# 2_interface.net
KiCad netlist of a schematic drawn in Altium Designer
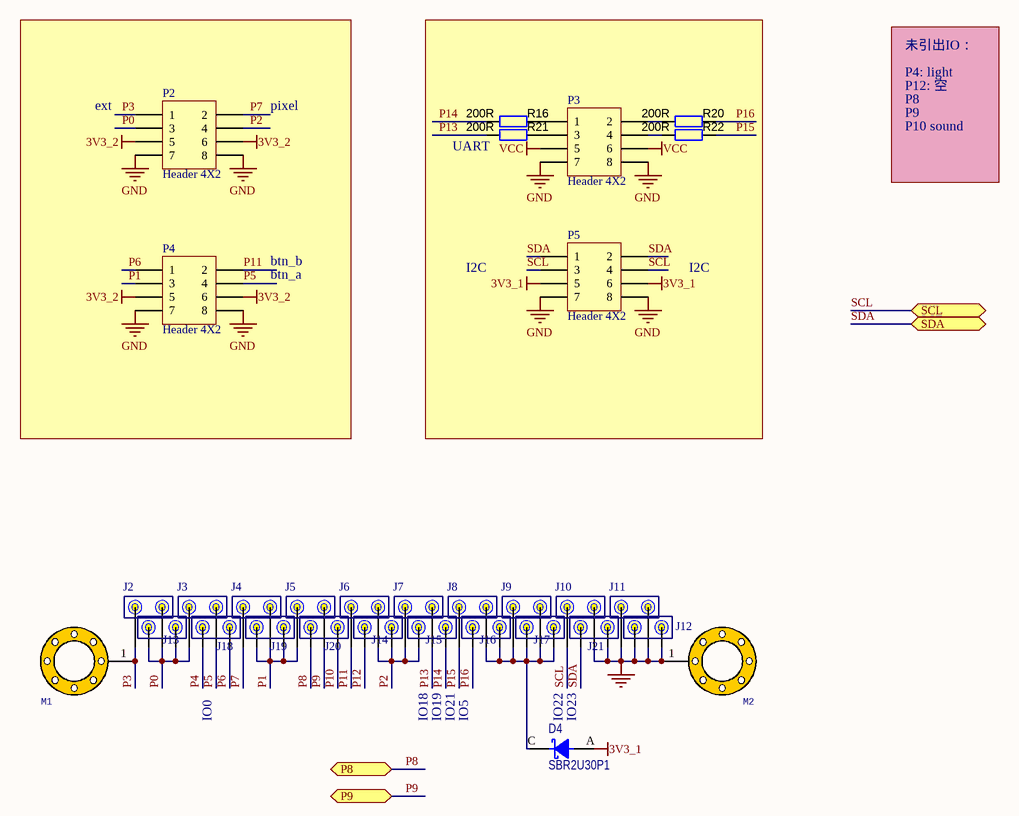
[diagram p0: 2.interface.SchDoc]

(export (version "E")
  (design (tool "Eeschema 10.0.6"))
  (components
    (comp (ref "D4")
      (value "SBR2U30P1")
      (footprint "POWERDI123")
      (fields (field (name "PARTNUMBER") "?") (field (name "PUBLISHER") "Altium Limited"))
      (libsource (lib "03.常用器件") (part "Diode_Schottky"))
    )
    (comp (ref "J2") (value "~") (footprint "顶针座子（2.54MM）") (libsource (lib "Schlib1") (part "pogopin")))
    (comp (ref "J3") (value "~") (footprint "顶针座子（2.54MM）") (libsource (lib "Schlib1") (part "pogopin")))
    (comp (ref "J4") (value "~") (footprint "顶针座子（2.54MM）") (libsource (lib "Schlib1") (part "pogopin")))
    (comp (ref "J5") (value "~") (footprint "顶针座子（2.54MM）") (libsource (lib "Schlib1") (part "pogopin")))
    (comp (ref "J6") (value "~") (footprint "顶针座子（2.54MM）") (libsource (lib "Schlib1") (part "pogopin")))
    (comp (ref "J7") (value "~") (footprint "顶针座子（2.54MM）") (libsource (lib "Schlib1") (part "pogopin")))
    (comp (ref "J8") (value "~") (footprint "顶针座子（2.54MM）") (libsource (lib "Schlib1") (part "pogopin")))
    (comp (ref "J9") (value "~") (footprint "顶针座子（2.54MM）") (libsource (lib "Schlib1") (part "pogopin")))
    (comp (ref "J10") (value "~") (footprint "顶针座子（2.54MM）") (libsource (lib "Schlib1") (part "pogopin")))
    (comp (ref "J11") (value "~") (footprint "顶针座子（2.54MM）") (libsource (lib "Schlib1") (part "pogopin")))
    (comp (ref "J12") (value "~") (footprint "顶针座子（2.54MM）") (libsource (lib "Schlib1") (part "pogopin_32")))
    (comp (ref "J13") (value "~") (footprint "顶针座子（2.54MM）") (libsource (lib "Schlib1") (part "pogopin_32")))
    (comp (ref "J14") (value "~") (footprint "顶针座子（2.54MM）") (libsource (lib "Schlib1") (part "pogopin_32")))
    (comp (ref "J15") (value "~") (footprint "顶针座子（2.54MM）") (libsource (lib "Schlib1") (part "pogopin_32")))
    (comp (ref "J16") (value "~") (footprint "顶针座子（2.54MM）") (libsource (lib "Schlib1") (part "pogopin_32")))
    (comp (ref "J17") (value "~") (footprint "顶针座子（2.54MM）") (libsource (lib "Schlib1") (part "pogopin_32")))
    (comp (ref "J18") (value "~") (footprint "顶针座子（2.54MM）") (libsource (lib "Schlib1") (part "pogopin_32")))
    (comp (ref "J19") (value "~") (footprint "顶针座子（2.54MM）") (libsource (lib "Schlib1") (part "pogopin_32")))
    (comp (ref "J20") (value "~") (footprint "顶针座子（2.54MM）") (libsource (lib "Schlib1") (part "pogopin_32")))
    (comp (ref "J21") (value "~") (footprint "顶针座子（2.54MM）") (libsource (lib "Schlib1") (part "pogopin_32")))
    (comp (ref "M1") (value "~") (footprint "3MM螺丝孔") (libsource (lib "labplus-connector") (part "screw")))
    (comp (ref "M2") (value "~") (footprint "3MM螺丝孔") (libsource (lib "labplus-connector") (part "screw")))
    (comp (ref "P2")
      (value "Header 4X2")
      (footprint "HDR2X4")
      (description "Header, 4-Pin, Dual row")
      (fields (field (name "PUBLISHER") "Altium Limited"))
      (libsource (lib "Miscellaneous Connectors") (part "Header 4X2"))
    )
    (comp (ref "P3")
      (value "Header 4X2")
      (footprint "HDR2X4")
      (description "Header, 4-Pin, Dual row")
      (fields (field (name "PUBLISHER") "Altium Limited"))
      (libsource (lib "Miscellaneous Connectors") (part "Header 4X2"))
    )
    (comp (ref "P4")
      (value "Header 4X2")
      (footprint "HDR2X4")
      (description "Header, 4-Pin, Dual row")
      (fields (field (name "PUBLISHER") "Altium Limited"))
      (libsource (lib "Miscellaneous Connectors") (part "Header 4X2"))
    )
    (comp (ref "P5")
      (value "Header 4X2")
      (footprint "HDR2X4")
      (description "Header, 4-Pin, Dual row")
      (fields (field (name "PUBLISHER") "Altium Limited"))
      (libsource (lib "Miscellaneous Connectors") (part "Header 4X2"))
    )
    (comp (ref "R16")
      (value "200R")
      (footprint "0402")
      (description "RES, 1.0k ohm, 5%, 0.1W, 0603")
      (fields
        (field (name "PARTNUMBER") "RC0603JR-071KL")
        (field (name "MANUFACTURER") "Yageo America")
        (field (name "PUBLISHER") "Texas Instruments")
      )
      (libsource (lib "03.常用器件") (part "RES1"))
    )
    (comp (ref "R20")
      (value "200R")
      (footprint "0402")
      (description "RES, 1.0k ohm, 5%, 0.1W, 0603")
      (fields
        (field (name "PARTNUMBER") "RC0603JR-071KL")
        (field (name "MANUFACTURER") "Yageo America")
        (field (name "PUBLISHER") "Texas Instruments")
      )
      (libsource (lib "03.常用器件") (part "RES1"))
    )
    (comp (ref "R21")
      (value "200R")
      (footprint "0402")
      (description "RES, 1.0k ohm, 5%, 0.1W, 0603")
      (fields
        (field (name "PARTNUMBER") "RC0603JR-071KL")
        (field (name "MANUFACTURER") "Yageo America")
        (field (name "PUBLISHER") "Texas Instruments")
      )
      (libsource (lib "03.常用器件") (part "RES1"))
    )
    (comp (ref "R22")
      (value "200R")
      (footprint "0402")
      (description "RES, 1.0k ohm, 5%, 0.1W, 0603")
      (fields
        (field (name "PARTNUMBER") "RC0603JR-071KL")
        (field (name "MANUFACTURER") "Yageo America")
        (field (name "PUBLISHER") "Texas Instruments")
      )
      (libsource (lib "03.常用器件") (part "RES1"))
    )
  )
  (nets
    (net (code "1") (name "/P0") (class "Default")
      (node (ref "J13") (pin "1") (pinfunction "1_1") (pintype "passive"))
      (node (ref "J13") (pin "2") (pinfunction "2_2") (pintype "passive"))
      (node (ref "J2") (pin "2") (pinfunction "2_2") (pintype "passive"))
      (node (ref "J3") (pin "1") (pinfunction "1_1") (pintype "passive"))
      (node (ref "P2") (pin "3") (pinfunction "3_3") (pintype "passive"))
    )
    (net (code "2") (name "/P1") (class "Default")
      (node (ref "J19") (pin "1") (pinfunction "1_1") (pintype "passive"))
      (node (ref "J19") (pin "2") (pinfunction "2_2") (pintype "passive"))
      (node (ref "J4") (pin "2") (pinfunction "2_2") (pintype "passive"))
      (node (ref "J5") (pin "1") (pinfunction "1_1") (pintype "passive"))
      (node (ref "P4") (pin "3") (pinfunction "3_3") (pintype "passive"))
    )
    (net (code "3") (name "/P2") (class "Default")
      (node (ref "J14") (pin "2") (pinfunction "2_2") (pintype "passive"))
      (node (ref "J15") (pin "1") (pinfunction "1_1") (pintype "passive"))
      (node (ref "J6") (pin "2") (pinfunction "2_2") (pintype "passive"))
      (node (ref "J7") (pin "1") (pinfunction "1_1") (pintype "passive"))
      (node (ref "P2") (pin "4") (pinfunction "4_4") (pintype "passive"))
    )
    (net (code "4") (name "/P3") (class "Default")
      (node (ref "J2") (pin "1") (pinfunction "1_1") (pintype "passive"))
      (node (ref "M1") (pin "1") (pinfunction "1_1") (pintype "passive"))
      (node (ref "P2") (pin "1") (pinfunction "1_1") (pintype "passive"))
    )
    (net (code "5") (name "/P4") (class "Default")
      (node (ref "J18") (pin "1") (pinfunction "1_1") (pintype "passive"))
    )
    (net (code "6") (name "/P5") (class "Default")
      (node (ref "J3") (pin "2") (pinfunction "2_2") (pintype "passive"))
      (node (ref "P4") (pin "4") (pinfunction "4_4") (pintype "passive"))
    )
    (net (code "7") (name "/P6") (class "Default")
      (node (ref "J18") (pin "2") (pinfunction "2_2") (pintype "passive"))
      (node (ref "P4") (pin "1") (pinfunction "1_1") (pintype "passive"))
    )
    (net (code "8") (name "/P7") (class "Default")
      (node (ref "J4") (pin "1") (pinfunction "1_1") (pintype "passive"))
      (node (ref "P2") (pin "2") (pinfunction "2_2") (pintype "passive"))
    )
    (net (code "9") (name "/P8") (class "Default")
      (node (ref "J20") (pin "1") (pinfunction "1_1") (pintype "passive"))
    )
    (net (code "10") (name "/P9") (class "Default")
      (node (ref "J5") (pin "2") (pinfunction "2_2") (pintype "passive"))
    )
    (net (code "11") (name "/P10") (class "Default")
      (node (ref "J20") (pin "2") (pinfunction "2_2") (pintype "passive"))
    )
    (net (code "12") (name "/P11") (class "Default")
      (node (ref "J6") (pin "1") (pinfunction "1_1") (pintype "passive"))
      (node (ref "P4") (pin "2") (pinfunction "2_2") (pintype "passive"))
    )
    (net (code "13") (name "/P12") (class "Default")
      (node (ref "J14") (pin "1") (pinfunction "1_1") (pintype "passive"))
    )
    (net (code "14") (name "/P13") (class "Default")
      (node (ref "J7") (pin "2") (pinfunction "2_2") (pintype "passive"))
      (node (ref "R21") (pin "1") (pinfunction "1_1") (pintype "passive"))
    )
    (net (code "15") (name "/P14") (class "Default")
      (node (ref "J15") (pin "2") (pinfunction "2_2") (pintype "passive"))
      (node (ref "R16") (pin "1") (pinfunction "1_1") (pintype "passive"))
    )
    (net (code "16") (name "/P15") (class "Default")
      (node (ref "J8") (pin "1") (pinfunction "1_1") (pintype "passive"))
      (node (ref "R22") (pin "2") (pinfunction "2_2") (pintype "passive"))
    )
    (net (code "17") (name "/P16") (class "Default")
      (node (ref "J16") (pin "1") (pinfunction "1_1") (pintype "passive"))
      (node (ref "R20") (pin "2") (pinfunction "2_2") (pintype "passive"))
    )
    (net (code "18") (name "/SCL") (class "Default")
      (node (ref "J10") (pin "1") (pinfunction "1_1") (pintype "passive"))
      (node (ref "P5") (pin "3") (pinfunction "3_3") (pintype "passive"))
      (node (ref "P5") (pin "4") (pinfunction "4_4") (pintype "passive"))
    )
    (net (code "19") (name "/SDA") (class "Default")
      (node (ref "J21") (pin "1") (pinfunction "1_1") (pintype "passive"))
      (node (ref "P5") (pin "1") (pinfunction "1_1") (pintype "passive"))
      (node (ref "P5") (pin "2") (pinfunction "2_2") (pintype "passive"))
    )
    (net (code "20") (name "3V3_1") (class "Default")
      (node (ref "D4") (pin "A") (pinfunction "ANODE_A") (pintype "passive"))
      (node (ref "P5") (pin "5") (pinfunction "5_5") (pintype "passive"))
      (node (ref "P5") (pin "6") (pinfunction "6_6") (pintype "passive"))
    )
    (net (code "21") (name "3V3_2") (class "Default")
      (node (ref "P2") (pin "5") (pinfunction "5_5") (pintype "passive"))
      (node (ref "P2") (pin "6") (pinfunction "6_6") (pintype "passive"))
      (node (ref "P4") (pin "5") (pinfunction "5_5") (pintype "passive"))
      (node (ref "P4") (pin "6") (pinfunction "6_6") (pintype "passive"))
    )
    (net (code "22") (name "GND") (class "Default")
      (node (ref "J10") (pin "2") (pinfunction "2_2") (pintype "passive"))
      (node (ref "J11") (pin "1") (pinfunction "1_1") (pintype "passive"))
      (node (ref "J11") (pin "2") (pinfunction "2_2") (pintype "passive"))
      (node (ref "J12") (pin "1") (pinfunction "1_1") (pintype "passive"))
      (node (ref "J12") (pin "2") (pinfunction "2_2") (pintype "passive"))
      (node (ref "J21") (pin "2") (pinfunction "2_2") (pintype "passive"))
      (node (ref "M2") (pin "1") (pinfunction "1_1") (pintype "passive"))
      (node (ref "P2") (pin "7") (pinfunction "7_7") (pintype "passive"))
      (node (ref "P2") (pin "8") (pinfunction "8_8") (pintype "passive"))
      (node (ref "P3") (pin "7") (pinfunction "7_7") (pintype "passive"))
      (node (ref "P3") (pin "8") (pinfunction "8_8") (pintype "passive"))
      (node (ref "P4") (pin "7") (pinfunction "7_7") (pintype "passive"))
      (node (ref "P4") (pin "8") (pinfunction "8_8") (pintype "passive"))
      (node (ref "P5") (pin "7") (pinfunction "7_7") (pintype "passive"))
      (node (ref "P5") (pin "8") (pinfunction "8_8") (pintype "passive"))
    )
    (net (code "23") (name "Net-(D4-CATHODE)") (class "Default")
      (node (ref "D4") (pin "C") (pinfunction "CATHODE_C") (pintype "passive"))
      (node (ref "J16") (pin "2") (pinfunction "2_2") (pintype "passive"))
      (node (ref "J17") (pin "1") (pinfunction "1_1") (pintype "passive"))
      (node (ref "J17") (pin "2") (pinfunction "2_2") (pintype "passive"))
      (node (ref "J8") (pin "2") (pinfunction "2_2") (pintype "passive"))
      (node (ref "J9") (pin "1") (pinfunction "1_1") (pintype "passive"))
      (node (ref "J9") (pin "2") (pinfunction "2_2") (pintype "passive"))
    )
    (net (code "24") (name "Net-(P3-Pad1)") (class "Default")
      (node (ref "P3") (pin "1") (pinfunction "1_1") (pintype "passive"))
      (node (ref "R16") (pin "2") (pinfunction "2_2") (pintype "passive"))
    )
    (net (code "25") (name "Net-(P3-Pad2)") (class "Default")
      (node (ref "P3") (pin "2") (pinfunction "2_2") (pintype "passive"))
      (node (ref "R20") (pin "1") (pinfunction "1_1") (pintype "passive"))
    )
    (net (code "26") (name "Net-(P3-Pad3)") (class "Default")
      (node (ref "P3") (pin "3") (pinfunction "3_3") (pintype "passive"))
      (node (ref "R21") (pin "2") (pinfunction "2_2") (pintype "passive"))
    )
    (net (code "27") (name "Net-(P3-Pad4)") (class "Default")
      (node (ref "P3") (pin "4") (pinfunction "4_4") (pintype "passive"))
      (node (ref "R22") (pin "1") (pinfunction "1_1") (pintype "passive"))
    )
    (net (code "28") (name "VCC") (class "Default")
      (node (ref "P3") (pin "5") (pinfunction "5_5") (pintype "passive"))
      (node (ref "P3") (pin "6") (pinfunction "6_6") (pintype "passive"))
    )
  )
)
